# PCB_MOTEUR_V0_1b.net
KiCad netlist of a schematic drawn in EAGLE
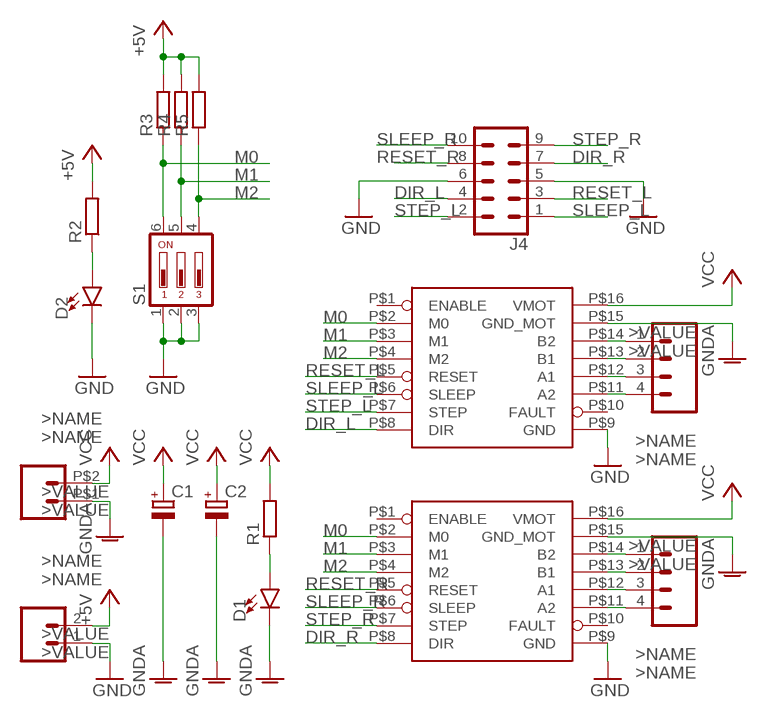
[diagram p0: schematic, sheet 1]

(export (version "E")
  (design (tool "Eeschema 10.0.6"))
  (components
    (comp (ref "C1")
      (value "CPOL-EUE3.5-8")
      (footprint "eagle-import:E3,5-8")
      (libsource (lib "eagle-import") (part "CPOL-EUE3.5-8"))
    )
    (comp (ref "C2")
      (value "CPOL-EUE3.5-8")
      (footprint "eagle-import:E3,5-8")
      (libsource (lib "eagle-import") (part "CPOL-EUE3.5-8"))
    )
    (comp (ref "D1")
      (value "LED3MM")
      (footprint "eagle-import:LED_3MM")
      (libsource (lib "eagle-import") (part "LED3MM"))
    )
    (comp (ref "D2")
      (value "LED3MM")
      (footprint "eagle-import:LED_3MM")
      (libsource (lib "eagle-import") (part "LED3MM"))
    )
    (comp (ref "J1")
      (value "CONN_02POLAR")
      (footprint "eagle-import:MOLEX-1X2")
      (libsource (lib "eagle-import") (part "CONN_02POLAR"))
    )
    (comp (ref "J2")
      (value "CONN_027A-C")
      (footprint "eagle-import:NSK396-2C")
      (libsource (lib "eagle-import") (part "CONN_027A-C"))
    )
    (comp (ref "J3")
      (value "CONN_04POLAR")
      (footprint "eagle-import:MOLEX-1X4")
      (libsource (lib "eagle-import") (part "CONN_04POLAR"))
    )
    (comp (ref "J4")
      (value "CONN_05X2SHD")
      (footprint "eagle-import:2X5-SHROUDED")
      (libsource (lib "eagle-import") (part "CONN_05X2SHD"))
    )
    (comp (ref "J5")
      (value "CONN_04POLAR")
      (footprint "eagle-import:MOLEX-1X4")
      (libsource (lib "eagle-import") (part "CONN_04POLAR"))
    )
    (comp (ref "R1")
      (value "R-EU_0207/2V")
      (footprint "eagle-import:0207_2V")
      (libsource (lib "eagle-import") (part "R-EU_0207/2V"))
    )
    (comp (ref "R2")
      (value "R-EU_0207/2V")
      (footprint "eagle-import:0207_2V")
      (libsource (lib "eagle-import") (part "R-EU_0207/2V"))
    )
    (comp (ref "R3")
      (value "R-EU_0207/10")
      (footprint "eagle-import:0207_10")
      (libsource (lib "eagle-import") (part "R-EU_0207/10"))
    )
    (comp (ref "R4")
      (value "R-EU_0207/10")
      (footprint "eagle-import:0207_10")
      (libsource (lib "eagle-import") (part "R-EU_0207/10"))
    )
    (comp (ref "R5")
      (value "R-EU_0207/10")
      (footprint "eagle-import:0207_10")
      (libsource (lib "eagle-import") (part "R-EU_0207/10"))
    )
    (comp (ref "S1")
      (value "DS03")
      (footprint "eagle-import:DS-03")
      (libsource (lib "eagle-import") (part "DS03"))
    )
    (comp (ref "U$1")
      (value "DRV8825")
      (footprint "eagle-import:DRIVER_CARRIER_POLOLU_16")
      (libsource (lib "eagle-import") (part "DRV8825"))
    )
    (comp (ref "U$2")
      (value "DRV8825")
      (footprint "eagle-import:DRIVER_CARRIER_POLOLU_16")
      (libsource (lib "eagle-import") (part "DRV8825"))
    )
  )
  (nets
    (net (code "1") (name "+5V") (class "Default")
      (node (ref "J1") (pin "2") (pinfunction "2_2") (pintype "passive"))
      (node (ref "R2") (pin "2") (pinfunction "2_2") (pintype "passive"))
      (node (ref "R3") (pin "2") (pinfunction "2_2") (pintype "passive"))
      (node (ref "R4") (pin "2") (pinfunction "2_2") (pintype "passive"))
      (node (ref "R5") (pin "2") (pinfunction "2_2") (pintype "passive"))
    )
    (net (code "2") (name "/DIR_L") (class "Default")
      (node (ref "J4") (pin "4") (pinfunction "4_4") (pintype "passive"))
      (node (ref "U$1") (pin "P$8") (pinfunction "DIR_P$8") (pintype "bidirectional"))
    )
    (net (code "3") (name "/DIR_R") (class "Default")
      (node (ref "J4") (pin "7") (pinfunction "7_7") (pintype "passive"))
      (node (ref "U$2") (pin "P$8") (pinfunction "DIR_P$8") (pintype "bidirectional"))
    )
    (net (code "4") (name "/M0") (class "Default")
      (node (ref "R3") (pin "1") (pinfunction "1_1") (pintype "passive"))
      (node (ref "S1") (pin "6") (pinfunction "6_6") (pintype "passive"))
      (node (ref "U$1") (pin "P$2") (pinfunction "M0_P$2") (pintype "bidirectional"))
      (node (ref "U$2") (pin "P$2") (pinfunction "M0_P$2") (pintype "bidirectional"))
    )
    (net (code "5") (name "/M1") (class "Default")
      (node (ref "R4") (pin "1") (pinfunction "1_1") (pintype "passive"))
      (node (ref "S1") (pin "5") (pinfunction "5_5") (pintype "passive"))
      (node (ref "U$1") (pin "P$3") (pinfunction "M1_P$3") (pintype "bidirectional"))
      (node (ref "U$2") (pin "P$3") (pinfunction "M1_P$3") (pintype "bidirectional"))
    )
    (net (code "6") (name "/M2") (class "Default")
      (node (ref "R5") (pin "1") (pinfunction "1_1") (pintype "passive"))
      (node (ref "S1") (pin "4") (pinfunction "4_4") (pintype "passive"))
      (node (ref "U$1") (pin "P$4") (pinfunction "M2_P$4") (pintype "bidirectional"))
      (node (ref "U$2") (pin "P$4") (pinfunction "M2_P$4") (pintype "bidirectional"))
    )
    (net (code "7") (name "/RESET_L") (class "Default")
      (node (ref "J4") (pin "3") (pinfunction "3_3") (pintype "passive"))
      (node (ref "U$1") (pin "P$5") (pinfunction "RESET_P$5") (pintype "bidirectional"))
    )
    (net (code "8") (name "/RESET_R") (class "Default")
      (node (ref "J4") (pin "8") (pinfunction "8_8") (pintype "passive"))
      (node (ref "U$2") (pin "P$5") (pinfunction "RESET_P$5") (pintype "bidirectional"))
    )
    (net (code "9") (name "/SLEEP_L") (class "Default")
      (node (ref "J4") (pin "1") (pinfunction "1_1") (pintype "passive"))
      (node (ref "U$1") (pin "P$6") (pinfunction "SLEEP_P$6") (pintype "bidirectional"))
    )
    (net (code "10") (name "/SLEEP_R") (class "Default")
      (node (ref "J4") (pin "10") (pinfunction "10_10") (pintype "passive"))
      (node (ref "U$2") (pin "P$6") (pinfunction "SLEEP_P$6") (pintype "bidirectional"))
    )
    (net (code "11") (name "/STEP_L") (class "Default")
      (node (ref "J4") (pin "2") (pinfunction "2_2") (pintype "passive"))
      (node (ref "U$1") (pin "P$7") (pinfunction "STEP_P$7") (pintype "bidirectional"))
    )
    (net (code "12") (name "/STEP_R") (class "Default")
      (node (ref "J4") (pin "9") (pinfunction "9_9") (pintype "passive"))
      (node (ref "U$2") (pin "P$7") (pinfunction "STEP_P$7") (pintype "bidirectional"))
    )
    (net (code "13") (name "GND") (class "Default")
      (node (ref "D2") (pin "K") (pinfunction "C_K") (pintype "passive"))
      (node (ref "J1") (pin "1") (pinfunction "1_1") (pintype "passive"))
      (node (ref "J4") (pin "5") (pinfunction "5_5") (pintype "passive"))
      (node (ref "J4") (pin "6") (pinfunction "6_6") (pintype "passive"))
      (node (ref "S1") (pin "1") (pinfunction "1_1") (pintype "passive"))
      (node (ref "S1") (pin "2") (pinfunction "2_2") (pintype "passive"))
      (node (ref "S1") (pin "3") (pinfunction "3_3") (pintype "passive"))
      (node (ref "U$1") (pin "P$9") (pinfunction "GND_P$9") (pintype "bidirectional"))
      (node (ref "U$2") (pin "P$9") (pinfunction "GND_P$9") (pintype "bidirectional"))
    )
    (net (code "14") (name "GNDA") (class "Default")
      (node (ref "C1") (pin "-") (pinfunction "-_-") (pintype "passive"))
      (node (ref "C2") (pin "-") (pinfunction "-_-") (pintype "passive"))
      (node (ref "D1") (pin "K") (pinfunction "C_K") (pintype "passive"))
      (node (ref "J2") (pin "P$1") (pinfunction "1_P$1") (pintype "passive"))
      (node (ref "U$1") (pin "P$15") (pinfunction "GND_MOT_P$15") (pintype "bidirectional"))
      (node (ref "U$2") (pin "P$15") (pinfunction "GND_MOT_P$15") (pintype "bidirectional"))
    )
    (net (code "15") (name "Net-(D1-PadA)") (class "Default")
      (node (ref "D1") (pin "A") (pinfunction "A_A") (pintype "passive"))
      (node (ref "R1") (pin "1") (pinfunction "1_1") (pintype "passive"))
    )
    (net (code "16") (name "Net-(D2-PadA)") (class "Default")
      (node (ref "D2") (pin "A") (pinfunction "A_A") (pintype "passive"))
      (node (ref "R2") (pin "1") (pinfunction "1_1") (pintype "passive"))
    )
    (net (code "17") (name "Net-(U$1-A1)") (class "Default")
      (node (ref "J3") (pin "3") (pinfunction "3_3") (pintype "passive"))
      (node (ref "U$1") (pin "P$12") (pinfunction "A1_P$12") (pintype "bidirectional"))
    )
    (net (code "18") (name "Net-(U$1-A2)") (class "Default")
      (node (ref "J3") (pin "4") (pinfunction "4_4") (pintype "passive"))
      (node (ref "U$1") (pin "P$11") (pinfunction "A2_P$11") (pintype "bidirectional"))
    )
    (net (code "19") (name "Net-(U$1-B1)") (class "Default")
      (node (ref "J3") (pin "2") (pinfunction "2_2") (pintype "passive"))
      (node (ref "U$1") (pin "P$13") (pinfunction "B1_P$13") (pintype "bidirectional"))
    )
    (net (code "20") (name "Net-(U$1-B2)") (class "Default")
      (node (ref "J3") (pin "1") (pinfunction "1_1") (pintype "passive"))
      (node (ref "U$1") (pin "P$14") (pinfunction "B2_P$14") (pintype "bidirectional"))
    )
    (net (code "21") (name "Net-(U$2-A1)") (class "Default")
      (node (ref "J5") (pin "3") (pinfunction "3_3") (pintype "passive"))
      (node (ref "U$2") (pin "P$12") (pinfunction "A1_P$12") (pintype "bidirectional"))
    )
    (net (code "22") (name "Net-(U$2-A2)") (class "Default")
      (node (ref "J5") (pin "4") (pinfunction "4_4") (pintype "passive"))
      (node (ref "U$2") (pin "P$11") (pinfunction "A2_P$11") (pintype "bidirectional"))
    )
    (net (code "23") (name "Net-(U$2-B1)") (class "Default")
      (node (ref "J5") (pin "2") (pinfunction "2_2") (pintype "passive"))
      (node (ref "U$2") (pin "P$13") (pinfunction "B1_P$13") (pintype "bidirectional"))
    )
    (net (code "24") (name "Net-(U$2-B2)") (class "Default")
      (node (ref "J5") (pin "1") (pinfunction "1_1") (pintype "passive"))
      (node (ref "U$2") (pin "P$14") (pinfunction "B2_P$14") (pintype "bidirectional"))
    )
    (net (code "25") (name "VCC") (class "Default")
      (node (ref "C1") (pin "+") (pinfunction "+_+") (pintype "passive"))
      (node (ref "C2") (pin "+") (pinfunction "+_+") (pintype "passive"))
      (node (ref "J2") (pin "P$2") (pinfunction "2_P$2") (pintype "passive"))
      (node (ref "R1") (pin "2") (pinfunction "2_2") (pintype "passive"))
      (node (ref "U$1") (pin "P$16") (pinfunction "VMOT_P$16") (pintype "bidirectional"))
      (node (ref "U$2") (pin "P$16") (pinfunction "VMOT_P$16") (pintype "bidirectional"))
    )
    (net (code "26") (name "unconnected-(U$1-ENABLE-PadP$1)") (class "Default")
      (node (ref "U$1") (pin "P$1") (pinfunction "ENABLE_P$1") (pintype "bidirectional"))
    )
    (net (code "27") (name "unconnected-(U$1-FAULT-PadP$10)") (class "Default")
      (node (ref "U$1") (pin "P$10") (pinfunction "FAULT_P$10") (pintype "bidirectional"))
    )
    (net (code "28") (name "unconnected-(U$2-ENABLE-PadP$1)") (class "Default")
      (node (ref "U$2") (pin "P$1") (pinfunction "ENABLE_P$1") (pintype "bidirectional"))
    )
    (net (code "29") (name "unconnected-(U$2-FAULT-PadP$10)") (class "Default")
      (node (ref "U$2") (pin "P$10") (pinfunction "FAULT_P$10") (pintype "bidirectional"))
    )
  )
)
